# REB215_XPRO_A_Connector.net
KiCad netlist of a schematic drawn in Altium Designer
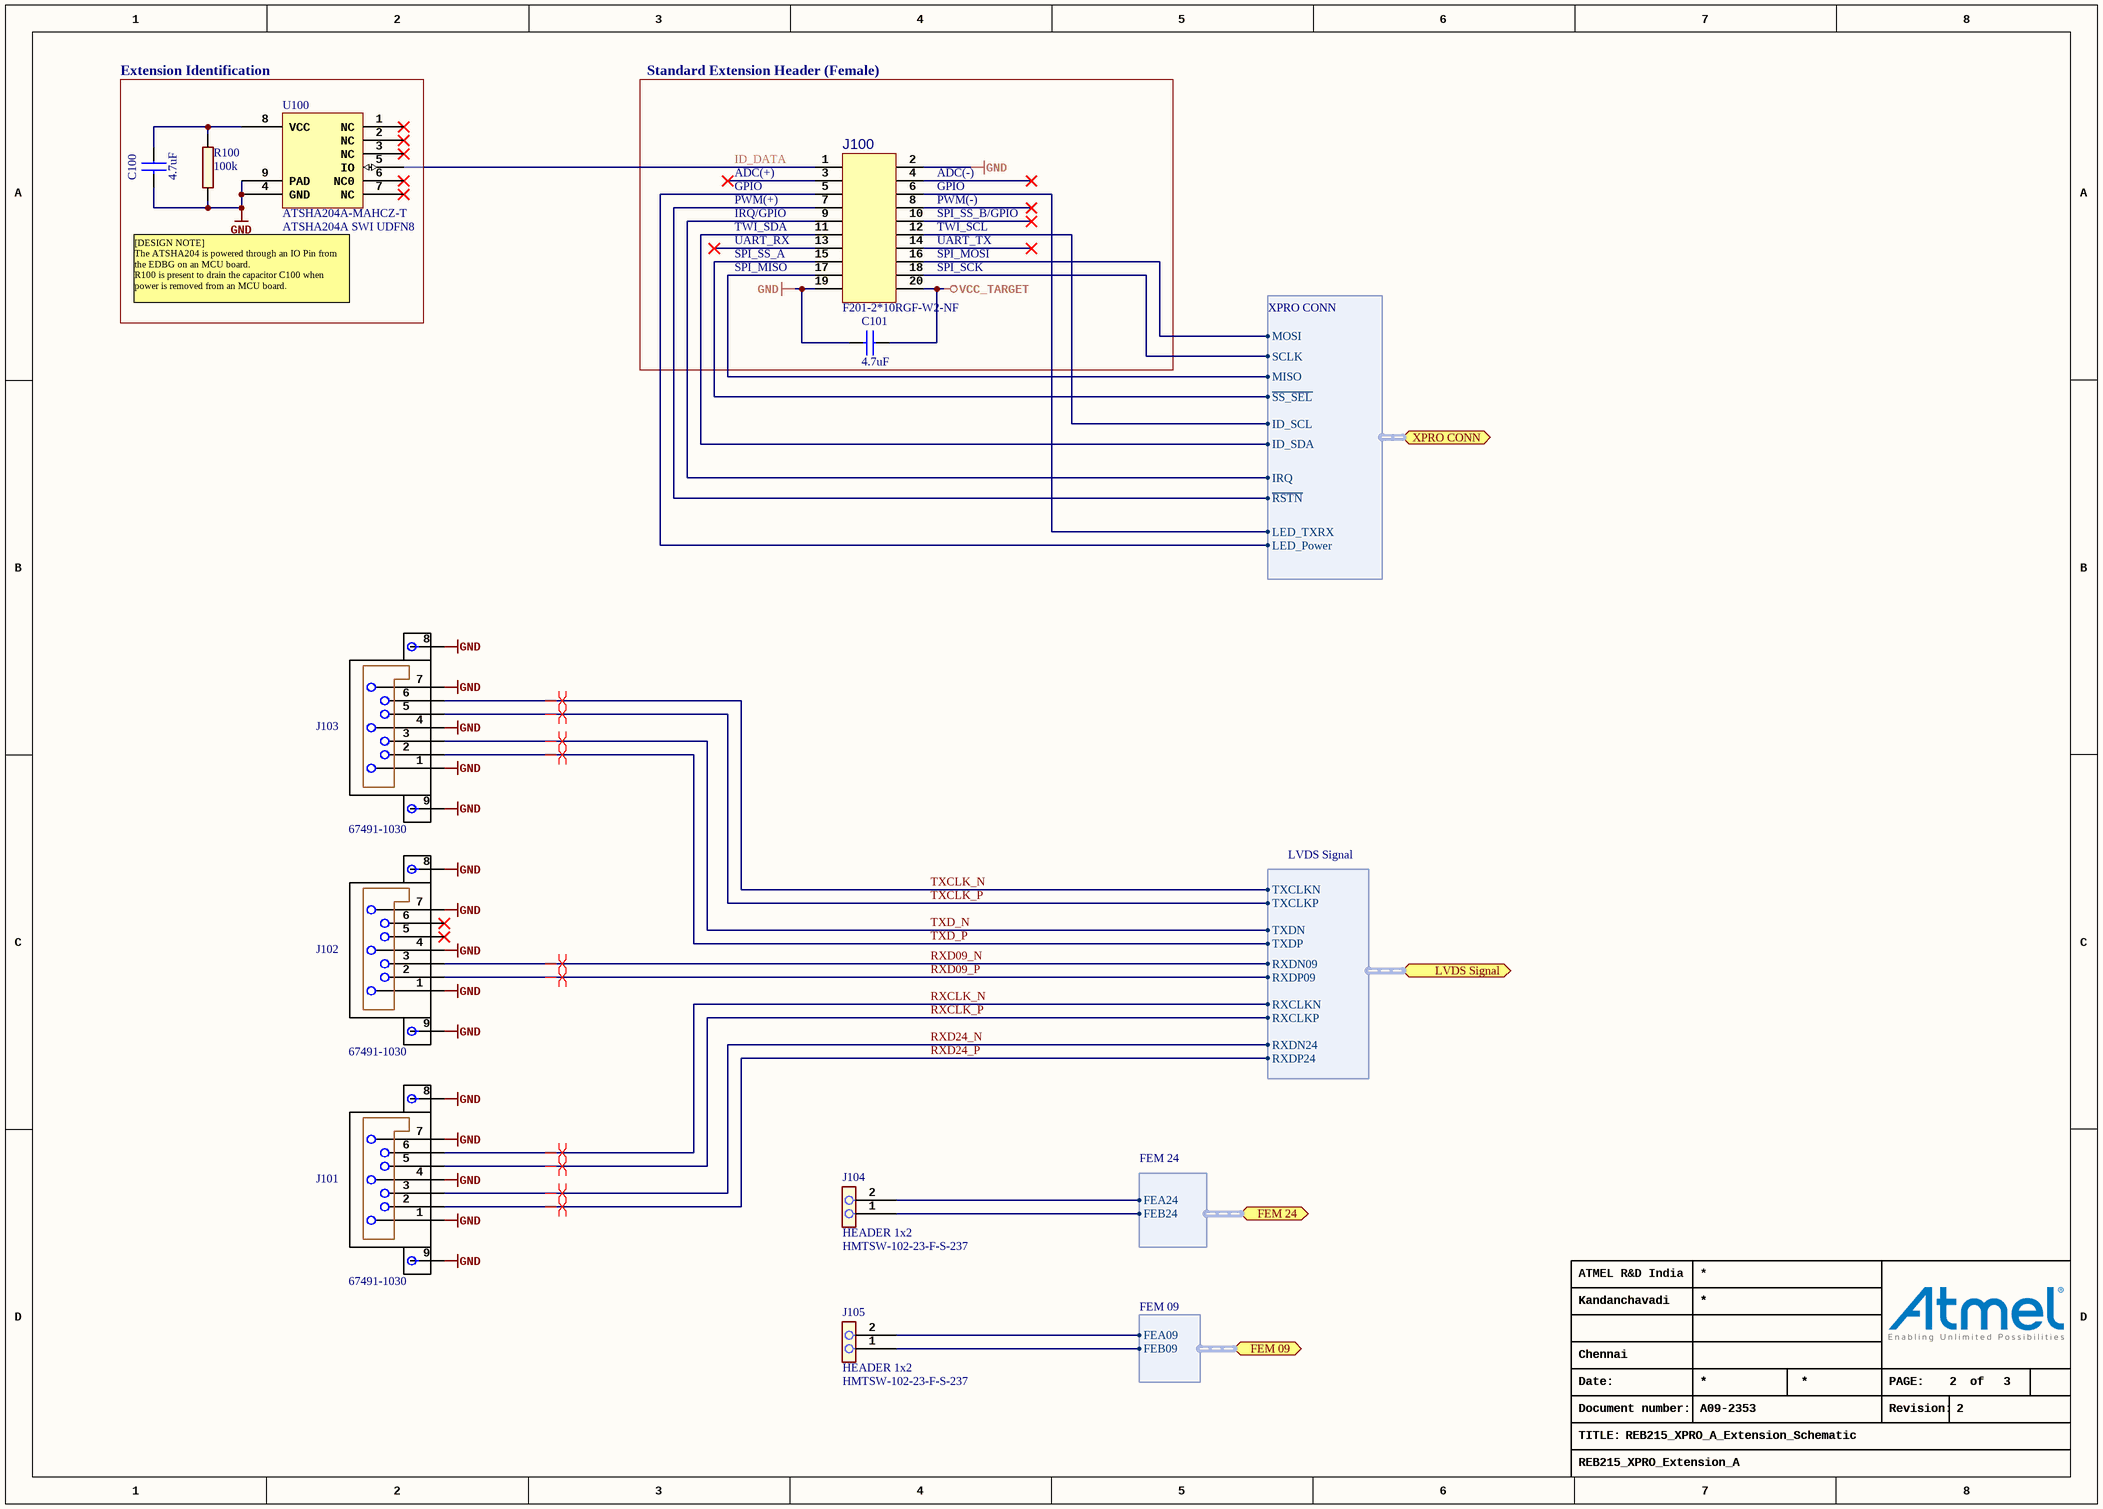
[diagram p0: REB215_XPRO_A_Connector.SchDoc]

(export (version "E")
  (design (tool "Eeschema 10.0.6"))
  (components
    (comp (ref "C100")
      (value "4.7uF")
      (footprint "AP1-00001")
      (description "Ceramic capacitor, SMD 0402, X5R, 6.3V, +/-20% (de33687)")
      (fields
        (field (name "TOLERANCE") "+-20%")
        (field (name "MANUFACTURER") "Murata")
        (field (name "VERIFIED BY") "Lars Helge Mo")
      )
      (libsource (lib "AltiumDbLib") (part "CAP-NONPOL"))
    )
    (comp (ref "C101")
      (value "4.7uF")
      (footprint "AP1-00001")
      (description "Ceramic capacitor, SMD 0402, X5R, 6.3V, +/-20% (de33687)")
      (fields
        (field (name "TOLERANCE") "+-20%")
        (field (name "MANUFACTURER") "Murata")
        (field (name "VERIFIED BY") "Lars Helge Mo")
      )
      (libsource (lib "AltiumDbLib") (part "CAP-NONPOL"))
    )
    (comp (ref "J100")
      (value "F201-2*10RGF-W2-NF")
      (footprint "AP8-00621")
      (description "2x10, female pin header receptable, right-angled, 2.54mm pitch, THM, Pin In Paste")
      (fields
        (field (name "MANUFACTURER") "Pro-data International Corp")
        (field (name "Comment") "HEADER-2X10")
        (field (name "VERIFIED BY") "*")
      )
      (libsource (lib "AltiumDbLib") (part "HEADER-2X10"))
    )
    (comp (ref "J101")
      (value "67491-1030")
      (footprint "AP8-00746")
      (description "1.27mm Pitch Serial ATA High Speed Header, Through Hole, Vertical, 7 Circuits")
      (fields
        (field (name "MANUFACTURER") "Molex")
        (field (name "Comment") "SATA_7PIN_HEADER")
        (field (name "VERIFIED BY") "vlarsen")
      )
      (libsource (lib "AltiumDbLib") (part "SATA_7PIN_HEADER"))
    )
    (comp (ref "J102")
      (value "67491-1030")
      (footprint "AP8-00746")
      (description "1.27mm Pitch Serial ATA High Speed Header, Through Hole, Vertical, 7 Circuits")
      (fields
        (field (name "MANUFACTURER") "Molex")
        (field (name "Comment") "SATA_7PIN_HEADER")
        (field (name "VERIFIED BY") "vlarsen")
      )
      (libsource (lib "AltiumDbLib") (part "SATA_7PIN_HEADER"))
    )
    (comp (ref "J103")
      (value "67491-1030")
      (footprint "AP8-00746")
      (description "1.27mm Pitch Serial ATA High Speed Header, Through Hole, Vertical, 7 Circuits")
      (fields
        (field (name "MANUFACTURER") "Molex")
        (field (name "Comment") "SATA_7PIN_HEADER")
        (field (name "VERIFIED BY") "vlarsen")
      )
      (libsource (lib "AltiumDbLib") (part "SATA_7PIN_HEADER"))
    )
    (comp (ref "J104")
      (value "HEADER 1x2")
      (footprint "AP8-00733")
      (description "1x2 pin header, 2.54mm pitch, Pin-in-Paste THM")
      (fields
        (field (name "ALTIUM_VALUE") "HMTSW-102-23-F-S-237")
        (field (name "MANUFACTURER") "SAMTEC")
        (field (name "MPN") "HMTSW-102-23-F-S-237")
        (field (name "VERIFIED BY") "Lars Helge")
      )
      (libsource (lib "AltiumDbLib") (part "HEADER 1x2"))
    )
    (comp (ref "J105")
      (value "HEADER 1x2")
      (footprint "AP8-00733")
      (description "1x2 pin header, 2.54mm pitch, Pin-in-Paste THM")
      (fields
        (field (name "ALTIUM_VALUE") "HMTSW-102-23-F-S-237")
        (field (name "MANUFACTURER") "SAMTEC")
        (field (name "MPN") "HMTSW-102-23-F-S-237")
        (field (name "VERIFIED BY") "Lars Helge")
      )
      (libsource (lib "AltiumDbLib") (part "HEADER 1x2"))
    )
    (comp (ref "R100")
      (value "100k")
      (footprint "AP2-00000")
      (description "Thick film resistor, SMD 0402, 1/16W, 1%")
      (fields
        (field (name "TOLERANCE") "1 %")
        (field (name "Comment") "R2")
        (field (name "VERIFIED BY") "Lars Helge Mo")
      )
      (libsource (lib "AltiumDbLib") (part "R2"))
    )
    (comp (ref "U100")
      (value "ATSHA204A-MAHCZ-T")
      (footprint "AP6-00409")
      (description "ATSHA204A with 1-wire interface and UDFN8 package")
      (fields
        (field (name "ALTIUM_VALUE") "ATSHA204A SWI UDFN8")
        (field (name "MANUFACTURER") "ATMEL")
        (field (name "VERIFIED BY") "VL")
      )
      (libsource (lib "AltiumDbLib") (part "ATSHA204A_SWI_UDFN"))
    )
  )
  (nets
    (net (code "8") (name "/FEA09") (class "Default")
      (node (ref "J105") (pin "2") (pinfunction "2_2") (pintype "passive"))
    )
    (net (code "9") (name "/FEA24") (class "Default")
      (node (ref "J104") (pin "2") (pinfunction "2_2") (pintype "passive"))
    )
    (net (code "10") (name "/FEB09") (class "Default")
      (node (ref "J105") (pin "1") (pinfunction "1_1") (pintype "passive"))
    )
    (net (code "11") (name "/FEB24") (class "Default")
      (node (ref "J104") (pin "1") (pinfunction "1_1") (pintype "passive"))
    )
    (net (code "12") (name "/ID_DATA") (class "Default")
      (node (ref "J100") (pin "1") (pintype "passive"))
      (node (ref "U100") (pin "5") (pinfunction "IO_5") (pintype "bidirectional"))
    )
    (net (code "13") (name "/ID_SCL") (class "Default") (node (ref "J100") (pin "12") (pintype "passive")))
    (net (code "14") (name "/ID_SDA") (class "Default") (node (ref "J100") (pin "11") (pintype "passive")))
    (net (code "15") (name "/IRQ") (class "Default") (node (ref "J100") (pin "9") (pintype "passive")))
    (net (code "16") (name "/LED_Power") (class "Default") (node (ref "J100") (pin "5") (pintype "passive")))
    (net (code "17") (name "/LED_TXRX") (class "Default") (node (ref "J100") (pin "6") (pintype "passive")))
    (net (code "18") (name "/MISO") (class "Default") (node (ref "J100") (pin "17") (pintype "passive")))
    (net (code "19") (name "/MOSI") (class "Default") (node (ref "J100") (pin "16") (pintype "passive")))
    (net (code "20") (name "/RXCLK_N") (class "Default")
      (node (ref "J101") (pin "6") (pinfunction "6_6") (pintype "passive"))
    )
    (net (code "21") (name "/RXCLK_P") (class "Default")
      (node (ref "J101") (pin "5") (pinfunction "5_5") (pintype "passive"))
    )
    (net (code "22") (name "/RXD09_N") (class "Default")
      (node (ref "J102") (pin "3") (pinfunction "3_3") (pintype "passive"))
    )
    (net (code "23") (name "/RXD09_P") (class "Default")
      (node (ref "J102") (pin "2") (pinfunction "2_2") (pintype "passive"))
    )
    (net (code "24") (name "/RXD24_N") (class "Default")
      (node (ref "J101") (pin "3") (pinfunction "3_3") (pintype "passive"))
    )
    (net (code "25") (name "/RXD24_P") (class "Default")
      (node (ref "J101") (pin "2") (pinfunction "2_2") (pintype "passive"))
    )
    (net (code "26") (name "/SCLK") (class "Default") (node (ref "J100") (pin "18") (pintype "passive")))
    (net (code "27") (name "/TXCLK_N") (class "Default")
      (node (ref "J103") (pin "6") (pinfunction "6_6") (pintype "passive"))
    )
    (net (code "28") (name "/TXCLK_P") (class "Default")
      (node (ref "J103") (pin "5") (pinfunction "5_5") (pintype "passive"))
    )
    (net (code "29") (name "/TXD_N") (class "Default")
      (node (ref "J103") (pin "3") (pinfunction "3_3") (pintype "passive"))
    )
    (net (code "30") (name "/TXD_P") (class "Default")
      (node (ref "J103") (pin "2") (pinfunction "2_2") (pintype "passive"))
    )
    (net (code "35") (name "/~{RSTN}") (class "Default") (node (ref "J100") (pin "7") (pintype "passive")))
    (net (code "36") (name "/~{SS_SEL}") (class "Default") (node (ref "J100") (pin "15") (pintype "passive")))
    (net (code "37") (name "GND") (class "Default")
      (node (ref "C100") (pin "2") (pinfunction "2_2") (pintype "passive"))
      (node (ref "C101") (pin "2") (pinfunction "2_2") (pintype "passive"))
      (node (ref "J100") (pin "19") (pintype "passive"))
      (node (ref "J100") (pin "2") (pintype "passive"))
      (node (ref "J101") (pin "1") (pinfunction "1_1") (pintype "passive"))
      (node (ref "J101") (pin "4") (pinfunction "4_4") (pintype "passive"))
      (node (ref "J101") (pin "7") (pinfunction "7_7") (pintype "passive"))
      (node (ref "J101") (pin "8") (pinfunction "8_8") (pintype "passive"))
      (node (ref "J101") (pin "9") (pinfunction "9_9") (pintype "passive"))
      (node (ref "J102") (pin "1") (pinfunction "1_1") (pintype "passive"))
      (node (ref "J102") (pin "4") (pinfunction "4_4") (pintype "passive"))
      (node (ref "J102") (pin "7") (pinfunction "7_7") (pintype "passive"))
      (node (ref "J102") (pin "8") (pinfunction "8_8") (pintype "passive"))
      (node (ref "J102") (pin "9") (pinfunction "9_9") (pintype "passive"))
      (node (ref "J103") (pin "1") (pinfunction "1_1") (pintype "passive"))
      (node (ref "J103") (pin "4") (pinfunction "4_4") (pintype "passive"))
      (node (ref "J103") (pin "7") (pinfunction "7_7") (pintype "passive"))
      (node (ref "J103") (pin "8") (pinfunction "8_8") (pintype "passive"))
      (node (ref "J103") (pin "9") (pinfunction "9_9") (pintype "passive"))
      (node (ref "R100") (pin "1") (pinfunction "1_1") (pintype "passive"))
      (node (ref "U100") (pin "4") (pinfunction "GND_4") (pintype "power_in"))
      (node (ref "U100") (pin "9") (pinfunction "PAD_9") (pintype "power_in"))
    )
    (net (code "38") (name "Net-(U100-VCC)") (class "Default")
      (node (ref "C100") (pin "1") (pinfunction "1_1") (pintype "passive"))
      (node (ref "R100") (pin "2") (pinfunction "2_2") (pintype "passive"))
      (node (ref "U100") (pin "8") (pinfunction "VCC_8") (pintype "power_in"))
    )
    (net (code "39") (name "VCC_TARGET") (class "Default")
      (node (ref "C101") (pin "1") (pinfunction "1_1") (pintype "passive"))
      (node (ref "J100") (pin "20") (pintype "passive"))
    )
    (net (code "40") (name "unconnected-(J100-Pad3)") (class "Default")
      (node (ref "J100") (pin "3") (pintype "passive+no_connect"))
    )
    (net (code "41") (name "unconnected-(J100-Pad4)") (class "Default")
      (node (ref "J100") (pin "4") (pintype "passive+no_connect"))
    )
    (net (code "42") (name "unconnected-(J100-Pad8)") (class "Default")
      (node (ref "J100") (pin "8") (pintype "passive+no_connect"))
    )
    (net (code "43") (name "unconnected-(J100-Pad10)") (class "Default")
      (node (ref "J100") (pin "10") (pintype "passive+no_connect"))
    )
    (net (code "44") (name "unconnected-(J100-Pad13)") (class "Default")
      (node (ref "J100") (pin "13") (pintype "passive+no_connect"))
    )
    (net (code "45") (name "unconnected-(J100-Pad14)") (class "Default")
      (node (ref "J100") (pin "14") (pintype "passive+no_connect"))
    )
    (net (code "46") (name "unconnected-(J102-Pad5)") (class "Default")
      (node (ref "J102") (pin "5") (pinfunction "5_5") (pintype "passive+no_connect"))
    )
    (net (code "47") (name "unconnected-(J102-Pad6)") (class "Default")
      (node (ref "J102") (pin "6") (pinfunction "6_6") (pintype "passive+no_connect"))
    )
    (net (code "48") (name "unconnected-(U100-NC-Pad1)") (class "Default")
      (node (ref "U100") (pin "1") (pinfunction "NC_1") (pintype "passive+no_connect"))
    )
    (net (code "49") (name "unconnected-(U100-NC-Pad2)") (class "Default")
      (node (ref "U100") (pin "2") (pinfunction "NC_2") (pintype "passive+no_connect"))
    )
    (net (code "50") (name "unconnected-(U100-NC-Pad3)") (class "Default")
      (node (ref "U100") (pin "3") (pinfunction "NC_3") (pintype "passive+no_connect"))
    )
    (net (code "51") (name "unconnected-(U100-NC-Pad7)") (class "Default")
      (node (ref "U100") (pin "7") (pinfunction "NC_7") (pintype "passive+no_connect"))
    )
    (net (code "52") (name "unconnected-(U100-NC0-Pad6)") (class "Default")
      (node (ref "U100") (pin "6") (pinfunction "NC0_6") (pintype "passive+no_connect"))
    )
  )
)
